# Schematic_Rev13.net
KiCad netlist of a schematic drawn in Altium Designer
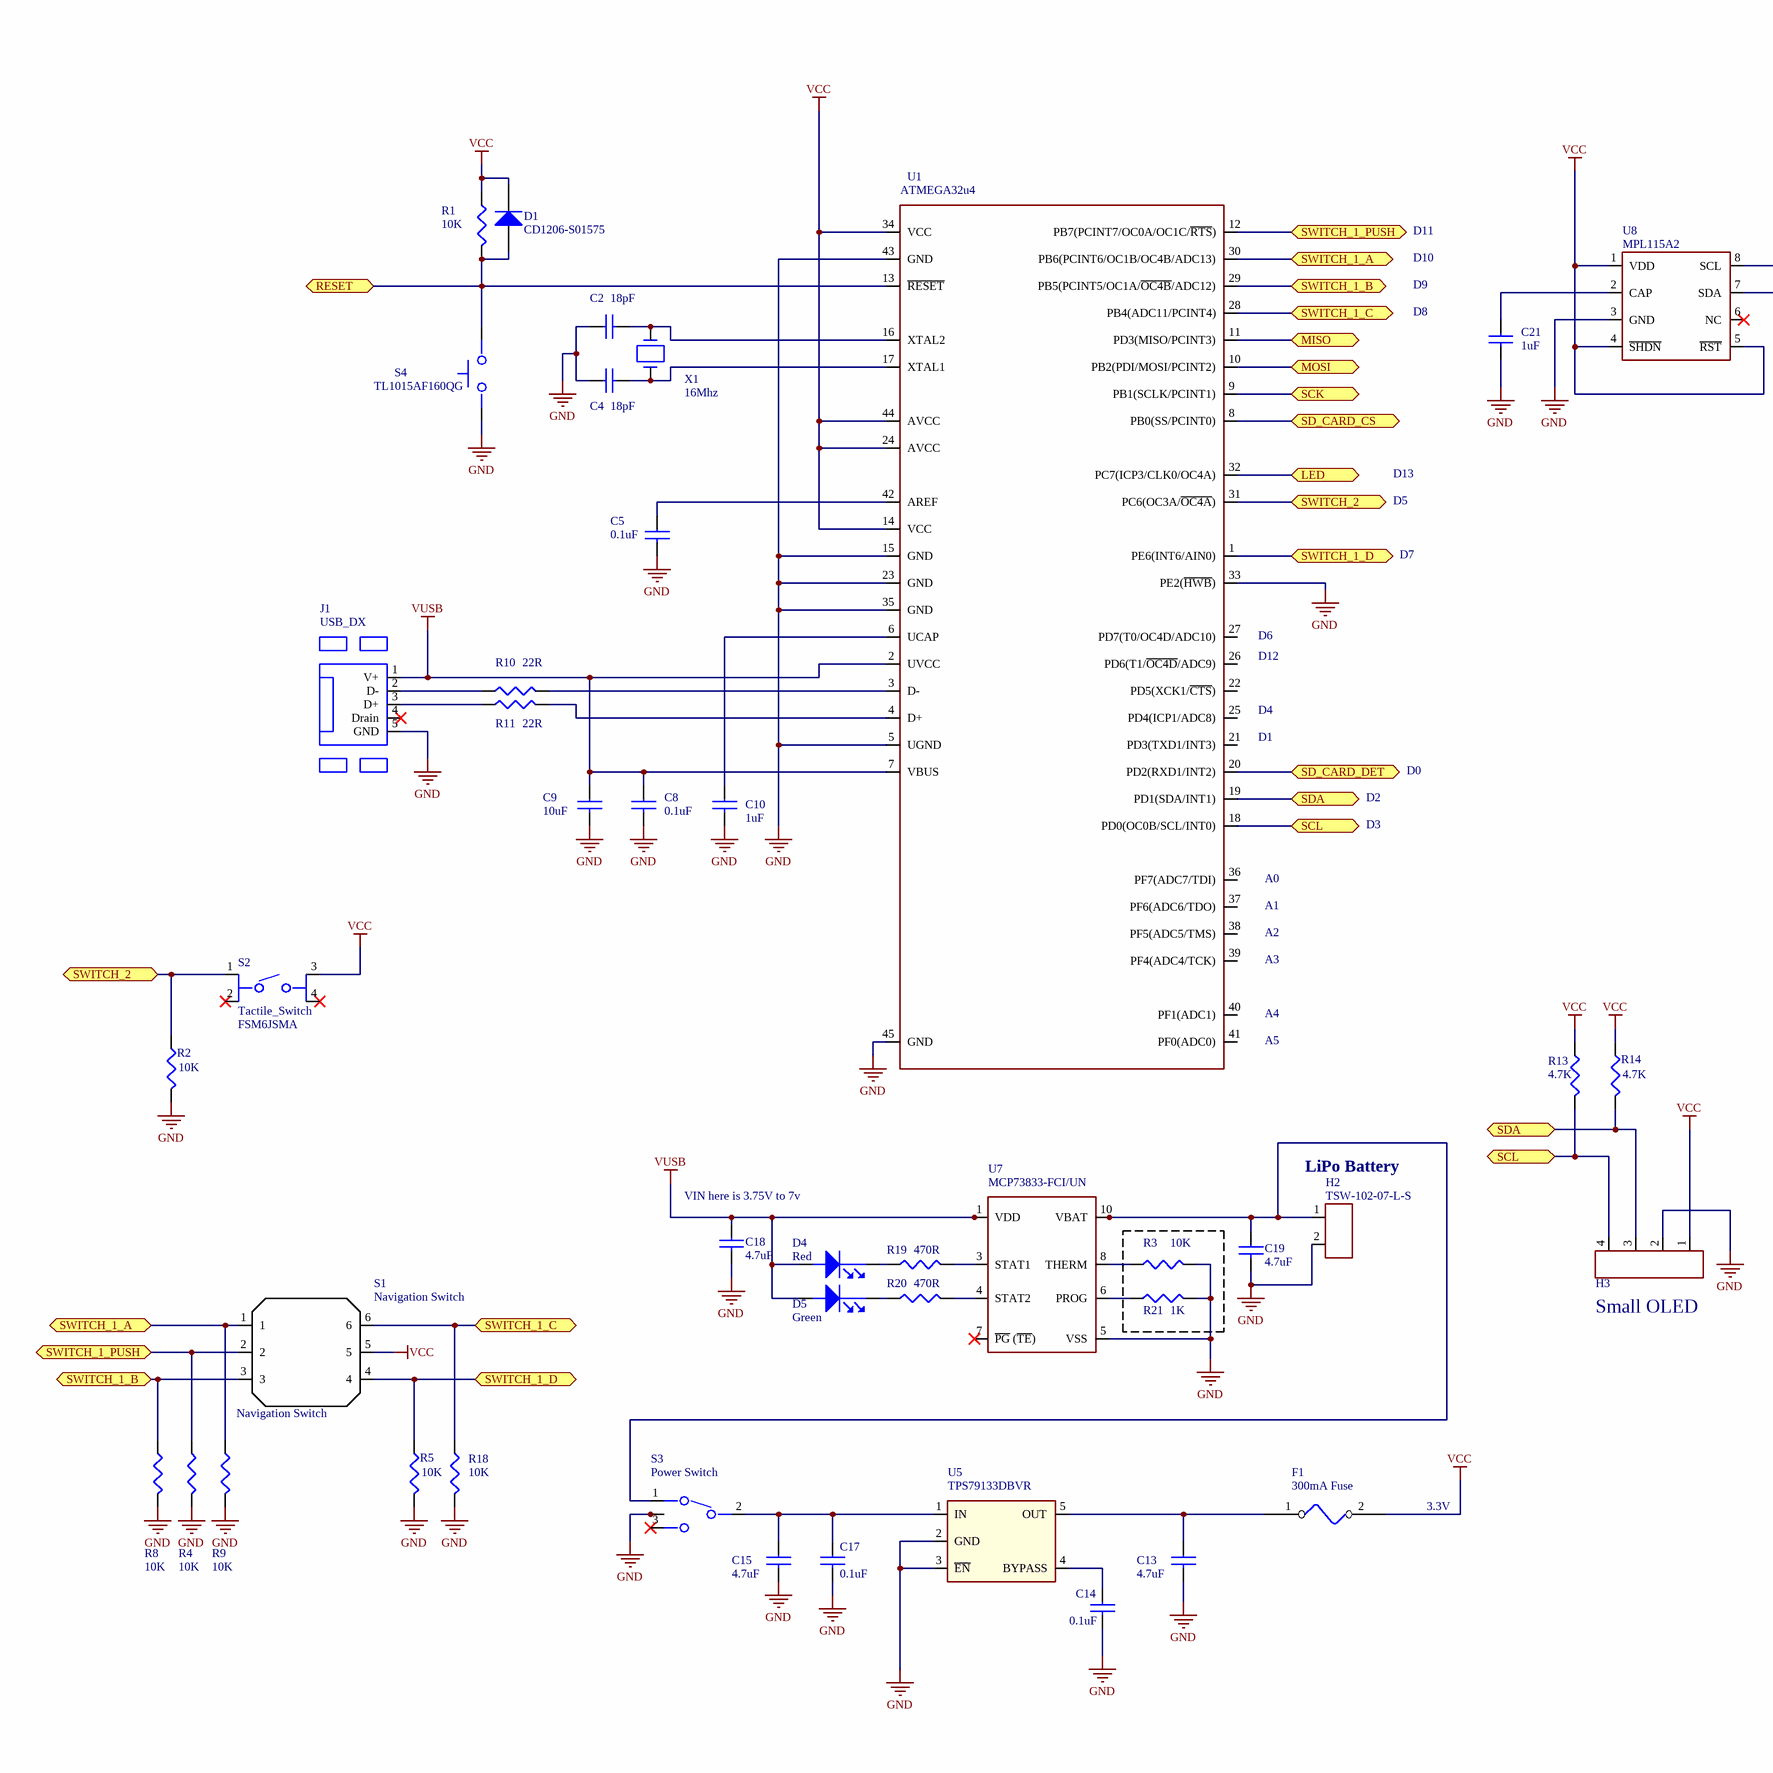
[diagram p0: Schematic_Rev13.SchDoc, left]
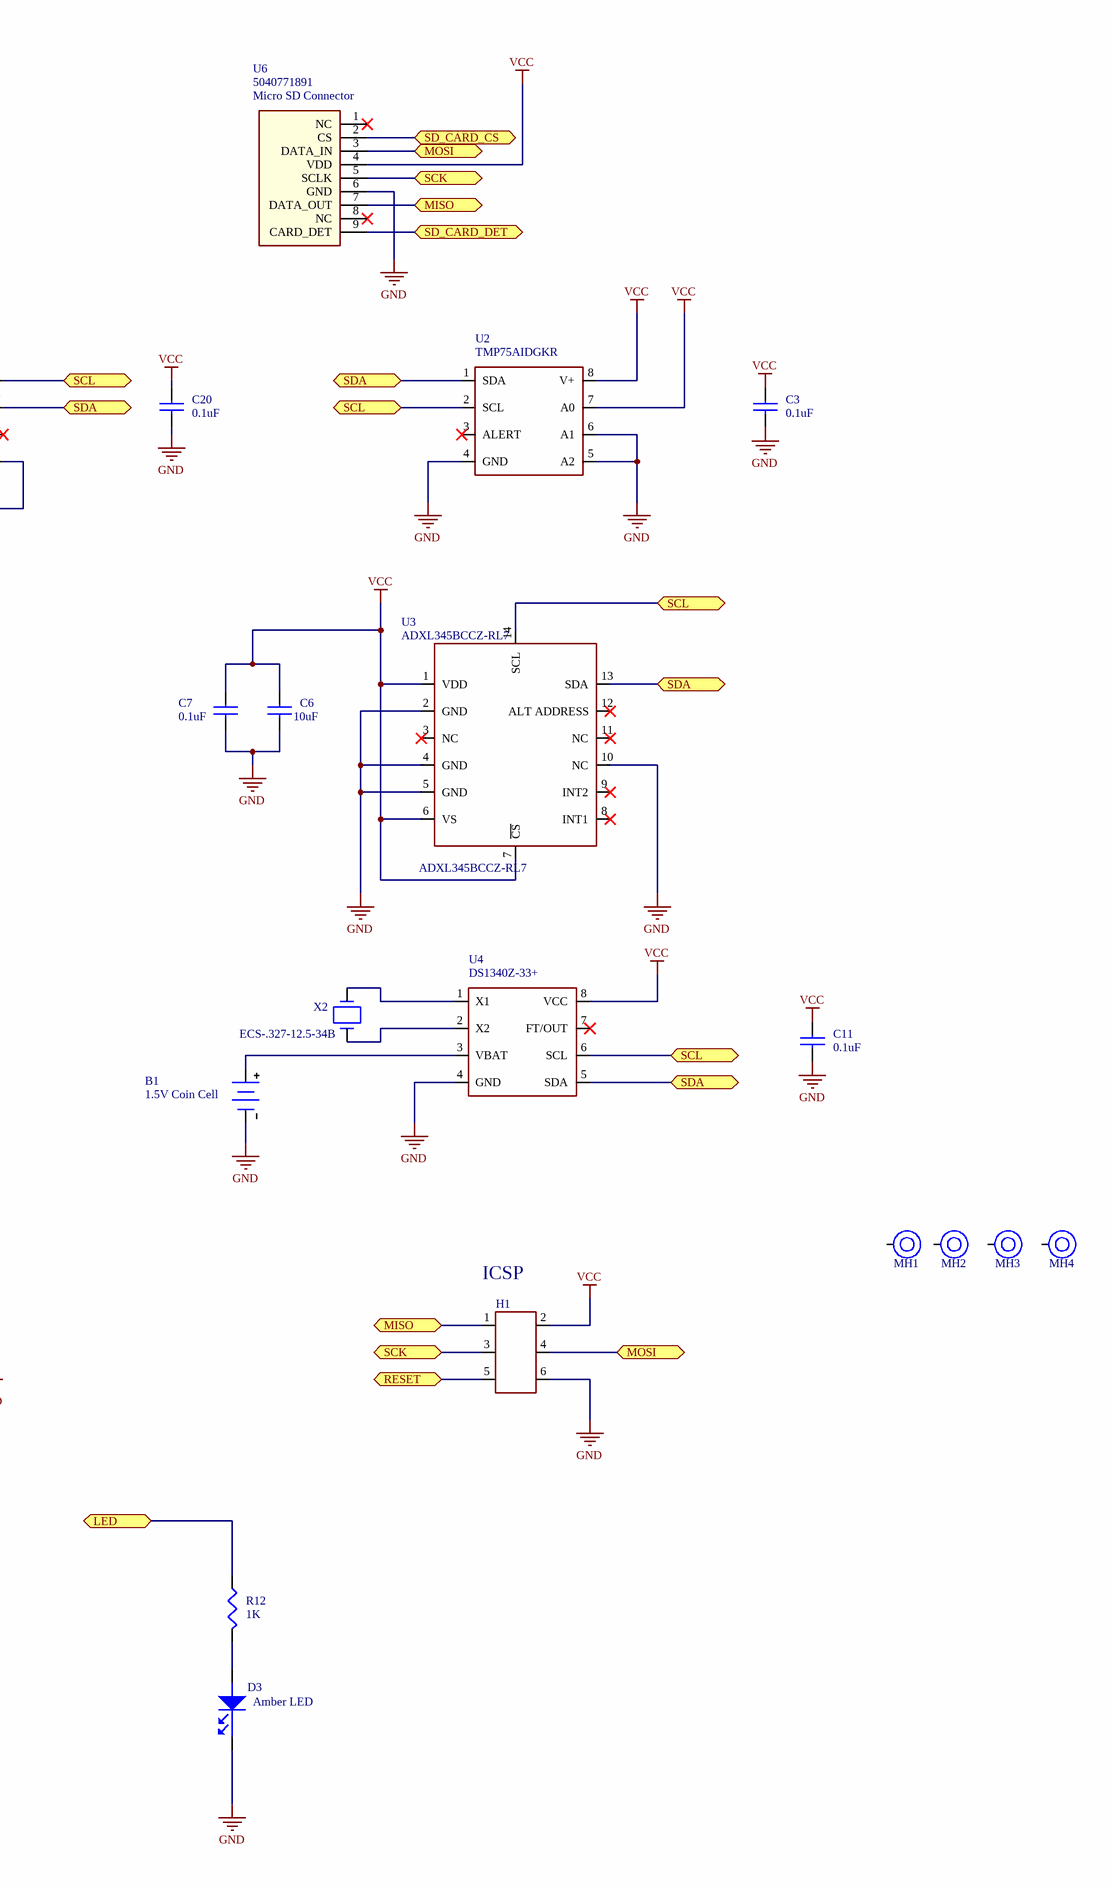
[diagram p1: Schematic_Rev13.SchDoc, right]

(export (version "E")
  (design (tool "Eeschema 10.0.6"))
  (components
    (comp (ref "B1")
      (value "1.5V Coin Cell")
      (footprint "CR377 Mount")
      (description "Custom CR377 mount")
      (fields (field (name "MANUFACTURER") "Sunbeam") (field (name "Comment") "CR377"))
      (libsource (lib "MAR") (part "CR377"))
    )
    (comp (ref "C2")
      (value "18pF")
      (footprint "CAPC1608X90N")
      (description "CAP CER 18pF 0603")
      (libsource (lib "Parts_Library") (part "CAP_0603"))
    )
    (comp (ref "C3")
      (value "0.1uF")
      (footprint "CAPC1608X90N")
      (description "CAP CER 0.1uF 0603")
      (libsource (lib "Parts_Library") (part "CAP_0603"))
    )
    (comp (ref "C4")
      (value "18pF")
      (footprint "CAPC1608X90N")
      (description "CAP CER 18pF 0603")
      (libsource (lib "Parts_Library") (part "CAP_0603"))
    )
    (comp (ref "C5")
      (value "0.1uF")
      (footprint "CAPC1608X90N")
      (description "CAP CER 0.1uF 0603")
      (libsource (lib "Parts_Library") (part "CAP_0603"))
    )
    (comp (ref "C6")
      (value "10uF")
      (footprint "CAPC3216X160N")
      (description "CAP CER 10UF 25V 10% X5R 1206")
      (fields (field (name "PARTNUMBER") "GRM31CR61E106KA12L") (field (name "MANUFACTURER") "Murata"))
      (libsource (lib "Parts_Library") (part "GRM31CR61E106KA12L"))
    )
    (comp (ref "C7")
      (value "0.1uF")
      (footprint "CAPC1608X90N")
      (description "CAP CER 0.1uF 0603")
      (libsource (lib "Parts_Library") (part "CAP_0603"))
    )
    (comp (ref "C8")
      (value "0.1uF")
      (footprint "CAPC1608X90N")
      (description "CAP 0603")
      (libsource (lib "Parts_Library") (part "CAP_0603"))
    )
    (comp (ref "C9")
      (value "10uF")
      (footprint "CAPC3216X160N")
      (description "CAP CER 10UF 25V 10% X5R 1206")
      (fields (field (name "PARTNUMBER") "GRM31CR61E106KA12L") (field (name "MANUFACTURER") "Murata"))
      (libsource (lib "Parts_Library") (part "GRM31CR61E106KA12L"))
    )
    (comp (ref "C10")
      (value "1uF")
      (footprint "CAPC1608X90N")
      (description "CAP CER 1uF 0603")
      (libsource (lib "Parts_Library") (part "CAP_0603"))
    )
    (comp (ref "C11")
      (value "0.1uF")
      (footprint "CAPC1608X90N")
      (description "CAP CER 0.1uF 0603")
      (libsource (lib "Parts_Library") (part "CAP_0603"))
    )
    (comp (ref "C13")
      (value "4.7uF")
      (footprint "CHIP_3216N")
      (description "CAP CER 4.7uF, 1206")
      (fields (field (name "Comment") "CAP_1206"))
      (libsource (lib "Parts_Library") (part "CAP_1206"))
    )
    (comp (ref "C14")
      (value "0.1uF")
      (footprint "CHIP_1608N")
      (description "CAP CER 0.1uF, 0603")
      (libsource (lib "Parts_Library") (part "CAP_0603"))
    )
    (comp (ref "C15")
      (value "4.7uF")
      (footprint "CHIP_3216N")
      (description "CAP CER 4.7uF, 1206")
      (fields (field (name "Comment") "CAP_1206"))
      (libsource (lib "Parts_Library") (part "CAP_1206"))
    )
    (comp (ref "C17")
      (value "0.1uF")
      (footprint "CHIP_1608N")
      (description "CAP CER 0.1uF, 0603")
      (libsource (lib "Parts_Library") (part "CAP_0603"))
    )
    (comp (ref "C18")
      (value "4.7uF")
      (footprint "CAPC3216X160N")
      (description "CAP CER 4.7uF, 1206")
      (libsource (lib "Parts_Library") (part "CAP_1206"))
    )
    (comp (ref "C19")
      (value "4.7uF")
      (footprint "CAPC3216X160N")
      (description "CAP CER 4.7uF, 1206")
      (libsource (lib "Parts_Library") (part "CAP_1206"))
    )
    (comp (ref "C20")
      (value "0.1uF")
      (footprint "CAPC1608X90N")
      (description "CAP 0603")
      (libsource (lib "Parts_Library") (part "CAP_0603"))
    )
    (comp (ref "C21")
      (value "1uF")
      (footprint "CAPC1608X90N")
      (description "CAP 0603")
      (libsource (lib "Parts_Library") (part "CAP_0603"))
    )
    (comp (ref "D1")
      (value "CD1206-S01575")
      (footprint "BOUR-CD1206-S01575-2_M")
      (description "75 V Small Signal Switching Diode, 150 mA, 2.5 uA, 1026 Molded Package, RoHS, Tape and Reel")
      (fields (field (name "MANUFACTURER") "Bourns"))
      (libsource (lib "Altium Content Vault") (part "CMP-0583-00001-2"))
    )
    (comp (ref "D3")
      (value "Amber LED")
      (footprint "LED1608X55N-RED")
      (description "LED_0603")
      (libsource (lib "Parts_Library") (part "LED_0603"))
    )
    (comp (ref "D4")
      (value "LED_0603")
      (footprint "LED1608X55N-GREEN")
      (fields (field (name "PARTNUMBER") "Red"))
      (libsource (lib "Parts_Library") (part "LED_0603"))
    )
    (comp (ref "D5")
      (value "LED_0603")
      (footprint "LED1608X55N-GREEN")
      (fields (field (name "PARTNUMBER") "Green"))
      (libsource (lib "Parts_Library") (part "LED_0603"))
    )
    (comp (ref "F1")
      (value "300mA Fuse")
      (footprint "RESC1608X55N")
      (description "FUSE .3A 125V FAST NANO2 SMD")
      (fields (field (name "PARTNUMBER") "MF-FSMF010X-2") (field (name "MANUFACTURER") "Bourns"))
      (libsource (lib "MAR") (part "MF-FSMF010X-2"))
    )
    (comp (ref "H1")
      (value "CON3X2")
      (footprint "HDR3X2")
      (description "CONN HEADER 3X2POS .100\" PADS")
      (fields (field (name "PARTNUMBER") "PADS"))
      (libsource (lib "Parts_Library") (part "CON3X2"))
    )
    (comp (ref "H2")
      (value "TSW-102-07-L-S")
      (footprint "HDR1X2")
      (description "CONN HEADER 2POS .100\" SGL GOLD")
      (fields (field (name "MANUFACTURER") "Samtec"))
      (libsource (lib "Parts_Library") (part "TSW-102-07-L-S"))
    )
    (comp (ref "H3")
      (value "CON4")
      (footprint "HDR1X4-Empty")
      (description "CONN HEADER 4POS .100\" PADS")
      (fields (field (name "PARTNUMBER") "PADS"))
      (libsource (lib "Parts_Library") (part "CON4"))
    )
    (comp (ref "J1")
      (value "USB_DX")
      (footprint "USB_DX")
      (description "CONN RECEPT MINIUSB R/A 5POS SMD")
      (libsource (lib "Parts_Library") (part "USB_DX"))
    )
    (comp (ref "MH1")
      (value "Mounting Hole")
      (footprint "MH - 128mil Hole, 250mil Pad")
      (libsource (lib "Parts_Library") (part "Mounting Hole"))
    )
    (comp (ref "MH2")
      (value "Mounting Hole")
      (footprint "MH - 128mil Hole, 250mil Pad")
      (libsource (lib "Parts_Library") (part "Mounting Hole"))
    )
    (comp (ref "MH3")
      (value "Mounting Hole")
      (footprint "MH - 128mil Hole, 250mil Pad")
      (libsource (lib "Parts_Library") (part "Mounting Hole"))
    )
    (comp (ref "MH4")
      (value "Mounting Hole")
      (footprint "MH - 128mil Hole, 250mil Pad")
      (libsource (lib "Parts_Library") (part "Mounting Hole"))
    )
    (comp (ref "R1")
      (value "10K")
      (footprint "RESC1608X55N")
      (description "RES 10K 0603")
      (libsource (lib "Parts_Library") (part "RES_0603"))
    )
    (comp (ref "R2")
      (value "10K")
      (footprint "RESC1608X55N")
      (description "RES 10K 0603")
      (libsource (lib "Parts_Library") (part "RES_0603"))
    )
    (comp (ref "R3")
      (value "10K")
      (footprint "RESC1608X55N")
      (description "RES 10K 0603")
      (fields (field (name "PARTNUMBER") "ERJ-3EKF1002V"))
      (libsource (lib "Parts_Library") (part "RES_0603"))
    )
    (comp (ref "R4")
      (value "10K")
      (footprint "RESC1608X55N")
      (description "RES 10K 0603")
      (libsource (lib "Parts_Library") (part "RES_0603"))
    )
    (comp (ref "R5")
      (value "10K")
      (footprint "RESC1608X55N")
      (description "RES 10K 0603")
      (libsource (lib "Parts_Library") (part "RES_0603"))
    )
    (comp (ref "R8")
      (value "10K")
      (footprint "RESC1608X55N")
      (description "RES 10K 0603")
      (libsource (lib "Parts_Library") (part "RES_0603"))
    )
    (comp (ref "R9")
      (value "10K")
      (footprint "RESC1608X55N")
      (description "RES 10K 0603")
      (libsource (lib "Parts_Library") (part "RES_0603"))
    )
    (comp (ref "R10")
      (value "22R")
      (footprint "RESC1608X55N")
      (description "RES 33R 0603")
      (libsource (lib "Parts_Library") (part "RES_0603"))
    )
    (comp (ref "R11")
      (value "22R")
      (footprint "RESC1608X55N")
      (description "RES 33R 0603")
      (libsource (lib "Parts_Library") (part "RES_0603"))
    )
    (comp (ref "R12")
      (value "1K")
      (footprint "RESC1608X55N")
      (description "RES 1K 0603")
      (libsource (lib "Parts_Library") (part "RES_0603"))
    )
    (comp (ref "R13")
      (value "4.7K")
      (footprint "RESC1608X55N")
      (description "RES 10K 0603")
      (libsource (lib "Parts_Library") (part "RES_0603"))
    )
    (comp (ref "R14")
      (value "4.7K")
      (footprint "RESC1608X55N")
      (description "RES 10K 0603")
      (libsource (lib "Parts_Library") (part "RES_0603"))
    )
    (comp (ref "R18")
      (value "10K")
      (footprint "RESC1608X55N")
      (description "RES 10K 0603")
      (libsource (lib "Parts_Library") (part "RES_0603"))
    )
    (comp (ref "R19")
      (value "470R")
      (footprint "RESC1608X55N")
      (libsource (lib "Parts_Library") (part "RES_0603"))
    )
    (comp (ref "R20")
      (value "470R")
      (footprint "RESC1608X55N")
      (libsource (lib "Parts_Library") (part "RES_0603"))
    )
    (comp (ref "R21")
      (value "1K")
      (footprint "RESC1608X55N")
      (description "RES 1K 0603")
      (fields (field (name "PARTNUMBER") "ERJ-3GEYJ102V"))
      (libsource (lib "Parts_Library") (part "RES_0603"))
    )
    (comp (ref "S1")
      (value "Navigation Switch")
      (footprint "NAVIGATION - DX")
      (description "Navigation Switch - DX")
      (fields (field (name "PARTNUMBER") "NAV-DX") (field (name "ALTIUM_VALUE") "Navigation Switch"))
      (libsource (lib "Parts_Library") (part "NAV-DX"))
    )
    (comp (ref "S2")
      (value "Tactile_Switch")
      (footprint "FSM6JSMA")
      (description "SWITCH TACTILE SPST-NO 0.05A 12V")
      (fields
        (field (name "MANUFACTURER") "TE Connectivity")
        (field (name "PARTNUMBER") "FSM6JSMA")
        (field (name "ALTIUM_VALUE") "FSM6JSMA")
      )
      (libsource (lib "Parts_Library") (part "FSM6JSMA"))
    )
    (comp (ref "S3")
      (value "~")
      (footprint "SLIDE_SWITCH_DX")
      (description "DX_SWITCH SLIDE SPDT R/A")
      (fields (field (name "PARTNUMBER") "122531"))
      (libsource (lib "MAR") (part "DX_SLIDE_SWITCH"))
    )
    (comp (ref "S4")
      (value "TL1015AF160QG")
      (footprint "TL1015AF160QG")
      (description "SWITCH TACTILE SPST-NO 0.05A 12V")
      (fields (field (name "MANUFACTURER") "E-Switch"))
      (libsource (lib "Parts_Library") (part "TL1015AF160QG"))
    )
    (comp (ref "U1")
      (value "ATMEGA32u4")
      (footprint "VQFN-44")
      (description "MCU AVR 32K FLASH 16MHZ 44-TQFP")
      (fields (field (name "PARTNUMBER") "ATMEGA32U4-AU") (field (name "MANUFACTURER") "Atmel"))
      (libsource (lib "Parts_Library") (part "ATmega32U4"))
    )
    (comp (ref "U2")
      (value "TMP75AIDGKR")
      (footprint "MSOP-8N - NOPAD")
      (description "IC DGTL TEMP SENSOR 2WIRE 8-MSOP")
      (fields (field (name "MANUFACTURER") "Maxim"))
      (libsource (lib "Parts_Library") (part "TMP75AIDGKR"))
    )
    (comp (ref "U3")
      (value "ADXL345BCCZ-RL7")
      (footprint "LGA80P300X500X100-14N")
      (description "IC ACCEL SPI/I2C 3AX 14LGA")
      (fields (field (name "MANUFACTURER") "Analog Devices") (field (name "ALTIUM_VALUE") "ADXL345BCCZ-RL7"))
      (libsource (lib "Parts_Library") (part "ADXL345BCCZ-RL7"))
    )
    (comp (ref "U4")
      (value "DS1340Z-33+")
      (footprint "TSOP65P490X110-8N")
      (description "IC RTC SERIAL 512K 8-TSSOP")
      (fields (field (name "MANUFACTURER") "Maxim"))
      (libsource (lib "Parts_Library") (part "DS1340Z-33+"))
    )
    (comp (ref "U5")
      (value "TPS79133DBVR")
      (footprint "SOT95P280X144-5N")
      (description "IC REG LDO 3.3V 0.1A SOT23-5")
      (fields (field (name "MANUFACTURER") "Texas Instruments") (field (name "PARTNUMBER") "TPS79133DBVR"))
      (libsource (lib "MAR") (part "TPS79133DBVR"))
    )
    (comp (ref "U6")
      (value "Micro SD Connector")
      (footprint "5040771891")
      (description "CONN MICRO SD CARD PUSH-PULL SMD")
      (fields (field (name "MANUFACTURER") "Molex") (field (name "PARTNUMBER") "5040771891"))
      (libsource (lib "MAR") (part "5040771891"))
    )
    (comp (ref "U7")
      (value "MCP73833-FCI/UN")
      (footprint "TSSOP50P490X110-10N")
      (description "IC LI-ION/LI-POLY CTRLR 10MSOP")
      (fields (field (name "MANUFACTURER") "Microchip") (field (name "PARTNUMBER") "MCP73833-FCI/UN"))
      (libsource (lib "Parts_Library") (part "MCP73833-FCI/UN"))
    )
    (comp (ref "U8")
      (value "MPL115A2")
      (footprint "8-LGA")
      (description "IC BAROMETER I2C DGTL MINI 8-LGA")
      (fields (field (name "MANUFACTURER") "Freescale"))
      (libsource (lib "Parts_Library") (part "MPL115A2"))
    )
    (comp (ref "X1")
      (value "16Mhz")
      (footprint "OSC320X250X75-4N")
      (description "CRYSTAL 16.000MHZ 18PF SMD")
      (fields (field (name "PARTNUMBER") "ABM8-16.000MHZ-B2-T") (field (name "MANUFACTURER") "Abracon"))
      (libsource (lib "Parts_Library") (part "ABM8-16.000MHZ-B2-T"))
    )
    (comp (ref "X2")
      (value "ECS-.327-12.5-34B")
      (footprint "ECS-.327-12.5-34B")
      (description "CRYSTAL 32.768 KHZ 12.5PF SMD")
      (fields (field (name "MANUFACTURER") "ECS"))
      (libsource (lib "Parts_Library") (part "ECS-.327-12.5-34B"))
    )
  )
  (nets
    (net (code "1") (name "/LED") (class "Default")
      (node (ref "R12") (pin "1") (pinfunction "1_1") (pintype "passive"))
      (node (ref "U1") (pin "32") (pinfunction "PC7(ICP3/CLK0/OC4A)_32") (pintype "passive"))
    )
    (net (code "2") (name "/MISO") (class "Default")
      (node (ref "H1") (pin "1") (pintype "passive"))
      (node (ref "U1") (pin "11") (pinfunction "PD3(MISO/PCINT3)_11") (pintype "passive"))
      (node (ref "U6") (pin "7") (pinfunction "DATA_OUT_7") (pintype "passive"))
    )
    (net (code "3") (name "/MOSI") (class "Default")
      (node (ref "H1") (pin "4") (pintype "passive"))
      (node (ref "U1") (pin "10") (pinfunction "PB2(PDI/MOSI/PCINT2)_10") (pintype "passive"))
      (node (ref "U6") (pin "3") (pinfunction "DATA_IN_3") (pintype "passive"))
    )
    (net (code "4") (name "/RESET") (class "Default")
      (node (ref "D1") (pin "1") (pinfunction "A_1") (pintype "passive"))
      (node (ref "H1") (pin "5") (pintype "passive"))
      (node (ref "R1") (pin "2") (pinfunction "2_2") (pintype "passive"))
      (node (ref "S4") (pin "2") (pinfunction "B_2") (pintype "passive"))
      (node (ref "U1") (pin "13") (pinfunction "~{RESET}_13") (pintype "passive"))
    )
    (net (code "5") (name "/SCK") (class "Default")
      (node (ref "H1") (pin "3") (pintype "passive"))
      (node (ref "U1") (pin "9") (pinfunction "PB1(SCLK/PCINT1)_9") (pintype "passive"))
      (node (ref "U6") (pin "5") (pinfunction "SCLK_5") (pintype "passive"))
    )
    (net (code "6") (name "/SCL") (class "Default")
      (node (ref "H3") (pin "4") (pintype "passive"))
      (node (ref "R13") (pin "2") (pinfunction "2_2") (pintype "passive"))
      (node (ref "U1") (pin "18") (pinfunction "PD0(OC0B/SCL/INT0)_18") (pintype "passive"))
      (node (ref "U2") (pin "2") (pinfunction "SCL_2") (pintype "passive"))
      (node (ref "U3") (pin "14") (pinfunction "SCL_14") (pintype "passive"))
      (node (ref "U4") (pin "6") (pinfunction "SCL_6") (pintype "passive"))
      (node (ref "U8") (pin "8") (pinfunction "SCL_8") (pintype "passive"))
    )
    (net (code "7") (name "/SDA") (class "Default")
      (node (ref "H3") (pin "3") (pintype "passive"))
      (node (ref "R14") (pin "2") (pinfunction "2_2") (pintype "passive"))
      (node (ref "U1") (pin "19") (pinfunction "PD1(SDA/INT1)_19") (pintype "passive"))
      (node (ref "U2") (pin "1") (pinfunction "SDA_1") (pintype "passive"))
      (node (ref "U3") (pin "13") (pinfunction "SDA_13") (pintype "passive"))
      (node (ref "U4") (pin "5") (pinfunction "SDA_5") (pintype "passive"))
      (node (ref "U8") (pin "7") (pinfunction "SDA_7") (pintype "passive"))
    )
    (net (code "8") (name "/SD_CARD_CS") (class "Default")
      (node (ref "U1") (pin "8") (pinfunction "PB0(SS/PCINT0)_8") (pintype "passive"))
      (node (ref "U6") (pin "2") (pinfunction "CS_2") (pintype "passive"))
    )
    (net (code "9") (name "/SD_CARD_DET") (class "Default")
      (node (ref "U1") (pin "20") (pinfunction "PD2(RXD1/INT2)_20") (pintype "passive"))
      (node (ref "U6") (pin "9") (pinfunction "CARD_DET_9") (pintype "passive"))
    )
    (net (code "10") (name "/SWITCH_1_A") (class "Default")
      (node (ref "R9") (pin "1") (pinfunction "1_1") (pintype "passive"))
      (node (ref "S1") (pin "1") (pinfunction "1_1") (pintype "passive"))
      (node (ref "U1") (pin "30") (pinfunction "PB6(PCINT6/OC1B/OC4B/ADC13)_30") (pintype "passive"))
    )
    (net (code "11") (name "/SWITCH_1_B") (class "Default")
      (node (ref "R8") (pin "1") (pinfunction "1_1") (pintype "passive"))
      (node (ref "S1") (pin "3") (pinfunction "3_3") (pintype "passive"))
      (node (ref "U1") (pin "29") (pinfunction "PB5(PCINT5/OC1A/~{OC4B}/ADC12)_29") (pintype "passive"))
    )
    (net (code "12") (name "/SWITCH_1_C") (class "Default")
      (node (ref "R18") (pin "1") (pinfunction "1_1") (pintype "passive"))
      (node (ref "S1") (pin "6") (pinfunction "6_6") (pintype "passive"))
      (node (ref "U1") (pin "28") (pinfunction "PB4(ADC11/PCINT4)_28") (pintype "passive"))
    )
    (net (code "13") (name "/SWITCH_1_D") (class "Default")
      (node (ref "R5") (pin "1") (pinfunction "1_1") (pintype "passive"))
      (node (ref "S1") (pin "4") (pinfunction "4_4") (pintype "passive"))
      (node (ref "U1") (pin "1") (pinfunction "PE6(INT6/AIN0)_1") (pintype "passive"))
    )
    (net (code "14") (name "/SWITCH_1_PUSH") (class "Default")
      (node (ref "R4") (pin "1") (pinfunction "1_1") (pintype "passive"))
      (node (ref "S1") (pin "2") (pinfunction "2_2") (pintype "passive"))
      (node (ref "U1") (pin "12") (pinfunction "PB7(PCINT7/OC0A/OC1C/~{RTS})_12") (pintype "passive"))
    )
    (net (code "15") (name "/SWITCH_2") (class "Default")
      (node (ref "R2") (pin "1") (pinfunction "1_1") (pintype "passive"))
      (node (ref "S2") (pin "1") (pintype "passive"))
      (node (ref "U1") (pin "31") (pinfunction "PC6(OC3A/~{OC4A})_31") (pintype "passive"))
    )
    (net (code "16") (name "GND") (class "Default")
      (node (ref "B1") (pin "2") (pinfunction "-_2") (pintype "passive"))
      (node (ref "C10") (pin "2") (pinfunction "2_2") (pintype "passive"))
      (node (ref "C11") (pin "2") (pinfunction "2_2") (pintype "passive"))
      (node (ref "C13") (pin "2") (pinfunction "2_2") (pintype "passive"))
      (node (ref "C14") (pin "2") (pinfunction "2_2") (pintype "passive"))
      (node (ref "C15") (pin "2") (pinfunction "2_2") (pintype "passive"))
      (node (ref "C17") (pin "2") (pinfunction "2_2") (pintype "passive"))
      (node (ref "C18") (pin "2") (pinfunction "2_2") (pintype "passive"))
      (node (ref "C19") (pin "2") (pinfunction "2_2") (pintype "passive"))
      (node (ref "C2") (pin "1") (pinfunction "1_1") (pintype "passive"))
      (node (ref "C20") (pin "2") (pinfunction "2_2") (pintype "passive"))
      (node (ref "C21") (pin "2") (pinfunction "2_2") (pintype "passive"))
      (node (ref "C3") (pin "2") (pinfunction "2_2") (pintype "passive"))
      (node (ref "C4") (pin "1") (pinfunction "1_1") (pintype "passive"))
      (node (ref "C5") (pin "2") (pinfunction "2_2") (pintype "passive"))
      (node (ref "C6") (pin "2") (pinfunction "2_2") (pintype "passive"))
      (node (ref "C7") (pin "2") (pinfunction "2_2") (pintype "passive"))
      (node (ref "C8") (pin "2") (pinfunction "2_2") (pintype "passive"))
      (node (ref "C9") (pin "2") (pinfunction "2_2") (pintype "passive"))
      (node (ref "D3") (pin "1") (pinfunction "CATHODE_1") (pintype "passive"))
      (node (ref "H1") (pin "6") (pintype "passive"))
      (node (ref "H2") (pin "2") (pintype "passive"))
      (node (ref "H3") (pin "2") (pintype "passive"))
      (node (ref "J1") (pin "5") (pinfunction "GND_5") (pintype "power_in"))
      (node (ref "R18") (pin "2") (pinfunction "2_2") (pintype "passive"))
      (node (ref "R2") (pin "2") (pinfunction "2_2") (pintype "passive"))
      (node (ref "R21") (pin "2") (pinfunction "2_2") (pintype "passive"))
      (node (ref "R3") (pin "2") (pinfunction "2_2") (pintype "passive"))
      (node (ref "R4") (pin "2") (pinfunction "2_2") (pintype "passive"))
      (node (ref "R5") (pin "2") (pinfunction "2_2") (pintype "passive"))
      (node (ref "R8") (pin "2") (pinfunction "2_2") (pintype "passive"))
      (node (ref "R9") (pin "2") (pinfunction "2_2") (pintype "passive"))
      (node (ref "S3") (pin "4") (pinfunction "GND_4") (pintype "passive"))
      (node (ref "S3") (pin "5") (pinfunction "GND_5") (pintype "passive"))
      (node (ref "S4") (pin "1") (pinfunction "A_1") (pintype "passive"))
      (node (ref "U1") (pin "15") (pinfunction "GND_15") (pintype "power_in"))
      (node (ref "U1") (pin "23") (pinfunction "GND_23") (pintype "power_in"))
      (node (ref "U1") (pin "33") (pinfunction "PE2(~{HWB})_33") (pintype "passive"))
      (node (ref "U1") (pin "35") (pinfunction "GND_35") (pintype "power_in"))
      (node (ref "U1") (pin "43") (pinfunction "GND_43") (pintype "power_in"))
      (node (ref "U1") (pin "45") (pinfunction "GND_45") (pintype "power_in"))
      (node (ref "U1") (pin "5") (pinfunction "UGND_5") (pintype "passive"))
      (node (ref "U2") (pin "4") (pinfunction "GND_4") (pintype "power_in"))
      (node (ref "U2") (pin "5") (pinfunction "A2_5") (pintype "passive"))
      (node (ref "U2") (pin "6") (pinfunction "A1_6") (pintype "passive"))
      (node (ref "U3") (pin "10") (pinfunction "NC_10") (pintype "passive"))
      (node (ref "U3") (pin "2") (pinfunction "GND_2") (pintype "power_in"))
      (node (ref "U3") (pin "4") (pinfunction "GND_4") (pintype "power_in"))
      (node (ref "U3") (pin "5") (pinfunction "GND_5") (pintype "power_in"))
      (node (ref "U4") (pin "4") (pinfunction "GND_4") (pintype "passive"))
      (node (ref "U5") (pin "2") (pinfunction "GND_2") (pintype "power_in"))
      (node (ref "U5") (pin "3") (pinfunction "~{EN}_3") (pintype "passive"))
      (node (ref "U6") (pin "6") (pinfunction "GND_6") (pintype "power_in"))
      (node (ref "U7") (pin "5") (pinfunction "VSS_5") (pintype "passive"))
      (node (ref "U8") (pin "3") (pinfunction "GND_3") (pintype "power_in"))
    )
    (net (code "17") (name "Net-(B1-+)") (class "Default")
      (node (ref "B1") (pin "1") (pinfunction "+_1") (pintype "passive"))
      (node (ref "U4") (pin "3") (pinfunction "VBAT_3") (pintype "passive"))
    )
    (net (code "18") (name "Net-(D3-ANODE)") (class "Default")
      (node (ref "D3") (pin "2") (pinfunction "ANODE_2") (pintype "passive"))
      (node (ref "R12") (pin "2") (pinfunction "2_2") (pintype "passive"))
    )
    (net (code "19") (name "Net-(D4-CATHODE)") (class "Default")
      (node (ref "D4") (pin "1") (pinfunction "CATHODE_1") (pintype "passive"))
      (node (ref "R19") (pin "1") (pinfunction "1_1") (pintype "passive"))
    )
    (net (code "20") (name "Net-(D5-CATHODE)") (class "Default")
      (node (ref "D5") (pin "1") (pinfunction "CATHODE_1") (pintype "passive"))
      (node (ref "R20") (pin "1") (pinfunction "1_1") (pintype "passive"))
    )
    (net (code "21") (name "Net-(J1-D+)") (class "Default")
      (node (ref "J1") (pin "3") (pinfunction "D+_3") (pintype "passive"))
      (node (ref "R11") (pin "1") (pinfunction "1_1") (pintype "passive"))
    )
    (net (code "22") (name "Net-(J1-D-)") (class "Default")
      (node (ref "J1") (pin "2") (pinfunction "D-_2") (pintype "passive"))
      (node (ref "R10") (pin "1") (pinfunction "1_1") (pintype "passive"))
    )
    (net (code "23") (name "Net-(S3-A)") (class "Default")
      (node (ref "C19") (pin "1") (pinfunction "1_1") (pintype "passive"))
      (node (ref "H2") (pin "1") (pintype "passive"))
      (node (ref "S3") (pin "1") (pinfunction "A_1") (pintype "passive"))
      (node (ref "U7") (pin "10") (pinfunction "VBAT_10") (pintype "power_in"))
      (node (ref "U7") (pin "9") (pinfunction "VBAT_9") (pintype "power_in"))
    )
    (net (code "24") (name "Net-(S3-Middle)") (class "Default")
      (node (ref "C15") (pin "1") (pinfunction "1_1") (pintype "passive"))
      (node (ref "C17") (pin "1") (pinfunction "1_1") (pintype "passive"))
      (node (ref "S3") (pin "2") (pinfunction "Middle_2") (pintype "passive"))
      (node (ref "U5") (pin "1") (pinfunction "IN_1") (pintype "power_in"))
    )
    (net (code "25") (name "Net-(U1-AREF)") (class "Default")
      (node (ref "C5") (pin "1") (pinfunction "1_1") (pintype "passive"))
      (node (ref "U1") (pin "42") (pinfunction "AREF_42") (pintype "passive"))
    )
    (net (code "26") (name "Net-(U1-D+)") (class "Default")
      (node (ref "R11") (pin "2") (pinfunction "2_2") (pintype "passive"))
      (node (ref "U1") (pin "4") (pinfunction "D+_4") (pintype "passive"))
    )
    (net (code "27") (name "Net-(U1-D-)") (class "Default")
      (node (ref "R10") (pin "2") (pinfunction "2_2") (pintype "passive"))
      (node (ref "U1") (pin "3") (pinfunction "D-_3") (pintype "passive"))
    )
    (net (code "28") (name "Net-(U1-UCAP)") (class "Default")
      (node (ref "C10") (pin "1") (pinfunction "1_1") (pintype "passive"))
      (node (ref "U1") (pin "6") (pinfunction "UCAP_6") (pintype "passive"))
    )
    (net (code "29") (name "Net-(U1-XTAL1)") (class "Default")
      (node (ref "C4") (pin "2") (pinfunction "2_2") (pintype "passive"))
      (node (ref "U1") (pin "17") (pinfunction "XTAL1_17") (pintype "passive"))
      (node (ref "X1") (pin "1") (pinfunction "1_1") (pintype "passive"))
    )
    (net (code "30") (name "Net-(U1-XTAL2)") (class "Default")
      (node (ref "C2") (pin "2") (pinfunction "2_2") (pintype "passive"))
      (node (ref "U1") (pin "16") (pinfunction "XTAL2_16") (pintype "passive"))
      (node (ref "X1") (pin "3") (pinfunction "3_3") (pintype "passive"))
    )
    (net (code "31") (name "Net-(U4-X1)") (class "Default")
      (node (ref "U4") (pin "1") (pinfunction "X1_1") (pintype "passive"))
      (node (ref "X2") (pin "1") (pinfunction "1_1") (pintype "passive"))
    )
    (net (code "32") (name "Net-(U4-X2)") (class "Default")
      (node (ref "U4") (pin "2") (pinfunction "X2_2") (pintype "passive"))
      (node (ref "X2") (pin "2") (pinfunction "2_2") (pintype "passive"))
    )
    (net (code "33") (name "Net-(U5-BYPASS)") (class "Default")
      (node (ref "C14") (pin "1") (pinfunction "1_1") (pintype "passive"))
      (node (ref "U5") (pin "4") (pinfunction "BYPASS_4") (pintype "passive"))
    )
    (net (code "34") (name "Net-(U5-OUT)") (class "Default")
      (node (ref "C13") (pin "1") (pinfunction "1_1") (pintype "passive"))
      (node (ref "F1") (pin "1") (pinfunction "1_1") (pintype "passive"))
      (node (ref "U5") (pin "5") (pinfunction "OUT_5") (pintype "passive"))
    )
    (net (code "35") (name "Net-(U7-PROG)") (class "Default")
      (node (ref "R21") (pin "1") (pinfunction "1_1") (pintype "passive"))
      (node (ref "U7") (pin "6") (pinfunction "PROG_6") (pintype "passive"))
    )
    (net (code "36") (name "Net-(U7-STAT1)") (class "Default")
      (node (ref "R19") (pin "2") (pinfunction "2_2") (pintype "passive"))
      (node (ref "U7") (pin "3") (pinfunction "STAT1_3") (pintype "passive"))
    )
    (net (code "37") (name "Net-(U7-STAT2)") (class "Default")
      (node (ref "R20") (pin "2") (pinfunction "2_2") (pintype "passive"))
      (node (ref "U7") (pin "4") (pinfunction "STAT2_4") (pintype "passive"))
    )
    (net (code "38") (name "Net-(U7-THERM)") (class "Default")
      (node (ref "R3") (pin "1") (pinfunction "1_1") (pintype "passive"))
      (node (ref "U7") (pin "8") (pinfunction "THERM_8") (pintype "passive"))
    )
    (net (code "39") (name "Net-(U8-CAP)") (class "Default")
      (node (ref "C21") (pin "1") (pinfunction "1_1") (pintype "passive"))
      (node (ref "U8") (pin "2") (pinfunction "CAP_2") (pintype "passive"))
    )
    (net (code "40") (name "VCC") (class "Default")
      (node (ref "C11") (pin "1") (pinfunction "1_1") (pintype "passive"))
      (node (ref "C20") (pin "1") (pinfunction "1_1") (pintype "passive"))
      (node (ref "C3") (pin "1") (pinfunction "1_1") (pintype "passive"))
      (node (ref "C6") (pin "1") (pinfunction "1_1") (pintype "passive"))
      (node (ref "C7") (pin "1") (pinfunction "1_1") (pintype "passive"))
      (node (ref "D1") (pin "2") (pinfunction "K_2") (pintype "passive"))
      (node (ref "F1") (pin "2") (pinfunction "2_2") (pintype "passive"))
      (node (ref "H1") (pin "2") (pintype "passive"))
      (node (ref "H3") (pin "1") (pintype "passive"))
      (node (ref "R1") (pin "1") (pinfunction "1_1") (pintype "passive"))
      (node (ref "R13") (pin "1") (pinfunction "1_1") (pintype "passive"))
      (node (ref "R14") (pin "1") (pinfunction "1_1") (pintype "passive"))
      (node (ref "S1") (pin "5") (pinfunction "5_5") (pintype "passive"))
      (node (ref "S2") (pin "3") (pintype "passive"))
      (node (ref "U1") (pin "14") (pinfunction "VCC_14") (pintype "power_in"))
      (node (ref "U1") (pin "24") (pinfunction "AVCC_24") (pintype "power_in"))
      (node (ref "U1") (pin "34") (pinfunction "VCC_34") (pintype "power_in"))
      (node (ref "U1") (pin "44") (pinfunction "AVCC_44") (pintype "passive"))
      (node (ref "U2") (pin "7") (pinfunction "A0_7") (pintype "passive"))
      (node (ref "U2") (pin "8") (pinfunction "V+_8") (pintype "power_in"))
      (node (ref "U3") (pin "1") (pinfunction "VDD_1") (pintype "power_in"))
      (node (ref "U3") (pin "6") (pinfunction "VS_6") (pintype "power_in"))
      (node (ref "U3") (pin "7") (pinfunction "~{CS}_7") (pintype "passive"))
      (node (ref "U4") (pin "8") (pinfunction "VCC_8") (pintype "power_in"))
      (node (ref "U6") (pin "4") (pinfunction "VDD_4") (pintype "power_in"))
      (node (ref "U8") (pin "1") (pinfunction "VDD_1") (pintype "power_in"))
      (node (ref "U8") (pin "4") (pinfunction "~{SHDN}_4") (pintype "passive"))
      (node (ref "U8") (pin "5") (pinfunction "~{RST}_5") (pintype "passive"))
    )
    (net (code "41") (name "VUSB") (class "Default")
      (node (ref "C18") (pin "1") (pinfunction "1_1") (pintype "passive"))
      (node (ref "C8") (pin "1") (pinfunction "1_1") (pintype "passive"))
      (node (ref "C9") (pin "1") (pinfunction "1_1") (pintype "passive"))
      (node (ref "D4") (pin "2") (pinfunction "ANODE_2") (pintype "passive"))
      (node (ref "D5") (pin "2") (pinfunction "ANODE_2") (pintype "passive"))
      (node (ref "J1") (pin "1") (pinfunction "V+_1") (pintype "power_in"))
      (node (ref "U1") (pin "2") (pinfunction "UVCC_2") (pintype "power_in"))
      (node (ref "U1") (pin "7") (pinfunction "VBUS_7") (pintype "passive"))
      (node (ref "U7") (pin "1") (pinfunction "VDD_1") (pintype "power_in"))
      (node (ref "U7") (pin "2") (pinfunction "VDD_2") (pintype "power_in"))
    )
    (net (code "42") (name "unconnected-(J1-Drain-Pad4)") (class "Default")
      (node (ref "J1") (pin "4") (pinfunction "Drain_4") (pintype "passive+no_connect"))
    )
    (net (code "43") (name "unconnected-(MH1-Pad1)") (class "Default")
      (node (ref "MH1") (pin "1") (pinfunction "1_1") (pintype "passive"))
    )
    (net (code "44") (name "unconnected-(MH2-Pad1)") (class "Default")
      (node (ref "MH2") (pin "1") (pinfunction "1_1") (pintype "passive"))
    )
    (net (code "45") (name "unconnected-(MH3-Pad1)") (class "Default")
      (node (ref "MH3") (pin "1") (pinfunction "1_1") (pintype "passive"))
    )
    (net (code "46") (name "unconnected-(MH4-Pad1)") (class "Default")
      (node (ref "MH4") (pin "1") (pinfunction "1_1") (pintype "passive"))
    )
    (net (code "47") (name "unconnected-(S2-Pad2)") (class "Default")
      (node (ref "S2") (pin "2") (pintype "passive+no_connect"))
    )
    (net (code "48") (name "unconnected-(S2-Pad4)") (class "Default")
      (node (ref "S2") (pin "4") (pintype "passive+no_connect"))
    )
    (net (code "49") (name "unconnected-(S3-B-Pad3)") (class "Default")
      (node (ref "S3") (pin "3") (pinfunction "B_3") (pintype "passive+no_connect"))
    )
    (net (code "50") (name "unconnected-(U1-PD3(TXD1{slash}INT3)-Pad21)") (class "Default")
      (node (ref "U1") (pin "21") (pinfunction "PD3(TXD1/INT3)_21") (pintype "passive"))
    )
    (net (code "51") (name "unconnected-(U1-PD4(ICP1{slash}ADC8)-Pad25)") (class "Default")
      (node (ref "U1") (pin "25") (pinfunction "PD4(ICP1/ADC8)_25") (pintype "passive"))
    )
    (net (code "52") (name "unconnected-(U1-PD5(XCK1{slash}~{CTS})-Pad22)") (class "Default")
      (node (ref "U1") (pin "22") (pinfunction "PD5(XCK1/~{CTS})_22") (pintype "passive"))
    )
    (net (code "53") (name "unconnected-(U1-PD6(T1{slash}~{OC4D}{slash}ADC9)-Pad26)") (class "Default")
      (node (ref "U1") (pin "26") (pinfunction "PD6(T1/~{OC4D}/ADC9)_26") (pintype "passive"))
    )
    (net (code "54") (name "unconnected-(U1-PD7(T0{slash}OC4D{slash}ADC10)-Pad27)") (class "Default")
      (node (ref "U1") (pin "27") (pinfunction "PD7(T0/OC4D/ADC10)_27") (pintype "passive"))
    )
    (net (code "55") (name "unconnected-(U1-PF0(ADC0)-Pad41)") (class "Default")
      (node (ref "U1") (pin "41") (pinfunction "PF0(ADC0)_41") (pintype "passive"))
    )
    (net (code "56") (name "unconnected-(U1-PF1(ADC1)-Pad40)") (class "Default")
      (node (ref "U1") (pin "40") (pinfunction "PF1(ADC1)_40") (pintype "passive"))
    )
    (net (code "57") (name "unconnected-(U1-PF4(ADC4{slash}TCK)-Pad39)") (class "Default")
      (node (ref "U1") (pin "39") (pinfunction "PF4(ADC4/TCK)_39") (pintype "passive"))
    )
    (net (code "58") (name "unconnected-(U1-PF5(ADC5{slash}TMS)-Pad38)") (class "Default")
      (node (ref "U1") (pin "38") (pinfunction "PF5(ADC5/TMS)_38") (pintype "passive"))
    )
    (net (code "59") (name "unconnected-(U1-PF6(ADC6{slash}TDO)-Pad37)") (class "Default")
      (node (ref "U1") (pin "37") (pinfunction "PF6(ADC6/TDO)_37") (pintype "passive"))
    )
    (net (code "60") (name "unconnected-(U1-PF7(ADC7{slash}TDI)-Pad36)") (class "Default")
      (node (ref "U1") (pin "36") (pinfunction "PF7(ADC7/TDI)_36") (pintype "passive"))
    )
    (net (code "61") (name "unconnected-(U2-ALERT-Pad3)") (class "Default")
      (node (ref "U2") (pin "3") (pinfunction "ALERT_3") (pintype "passive+no_connect"))
    )
    (net (code "62") (name "unconnected-(U3-ALT_ADDRESS-Pad12)") (class "Default")
      (node (ref "U3") (pin "12") (pinfunction "ALT_ADDRESS_12") (pintype "passive+no_connect"))
    )
    (net (code "63") (name "unconnected-(U3-INT1-Pad8)") (class "Default")
      (node (ref "U3") (pin "8") (pinfunction "INT1_8") (pintype "passive+no_connect"))
    )
    (net (code "64") (name "unconnected-(U3-INT2-Pad9)") (class "Default")
      (node (ref "U3") (pin "9") (pinfunction "INT2_9") (pintype "passive+no_connect"))
    )
    (net (code "65") (name "unconnected-(U3-NC-Pad3)") (class "Default")
      (node (ref "U3") (pin "3") (pinfunction "NC_3") (pintype "passive+no_connect"))
    )
    (net (code "66") (name "unconnected-(U3-NC-Pad11)") (class "Default")
      (node (ref "U3") (pin "11") (pinfunction "NC_11") (pintype "passive+no_connect"))
    )
    (net (code "67") (name "unconnected-(U4-FT{slash}OUT-Pad7)") (class "Default")
      (node (ref "U4") (pin "7") (pinfunction "FT/OUT_7") (pintype "passive+no_connect"))
    )
    (net (code "68") (name "unconnected-(U6-NC-Pad1)") (class "Default")
      (node (ref "U6") (pin "1") (pinfunction "NC_1") (pintype "passive+no_connect"))
    )
    (net (code "69") (name "unconnected-(U6-NC-Pad8)") (class "Default")
      (node (ref "U6") (pin "8") (pinfunction "NC_8") (pintype "passive+no_connect"))
    )
    (net (code "70") (name "unconnected-(U7-~{PG}_(~{TE})-Pad7)") (class "Default")
      (node (ref "U7") (pin "7") (pinfunction "~{PG}_(~{TE})_7") (pintype "passive+no_connect"))
    )
    (net (code "71") (name "unconnected-(U8-NC-Pad6)") (class "Default")
      (node (ref "U8") (pin "6") (pinfunction "NC_6") (pintype "passive+no_connect"))
    )
  )
)
